# levels.net
KiCad netlist of a schematic drawn in EAGLE
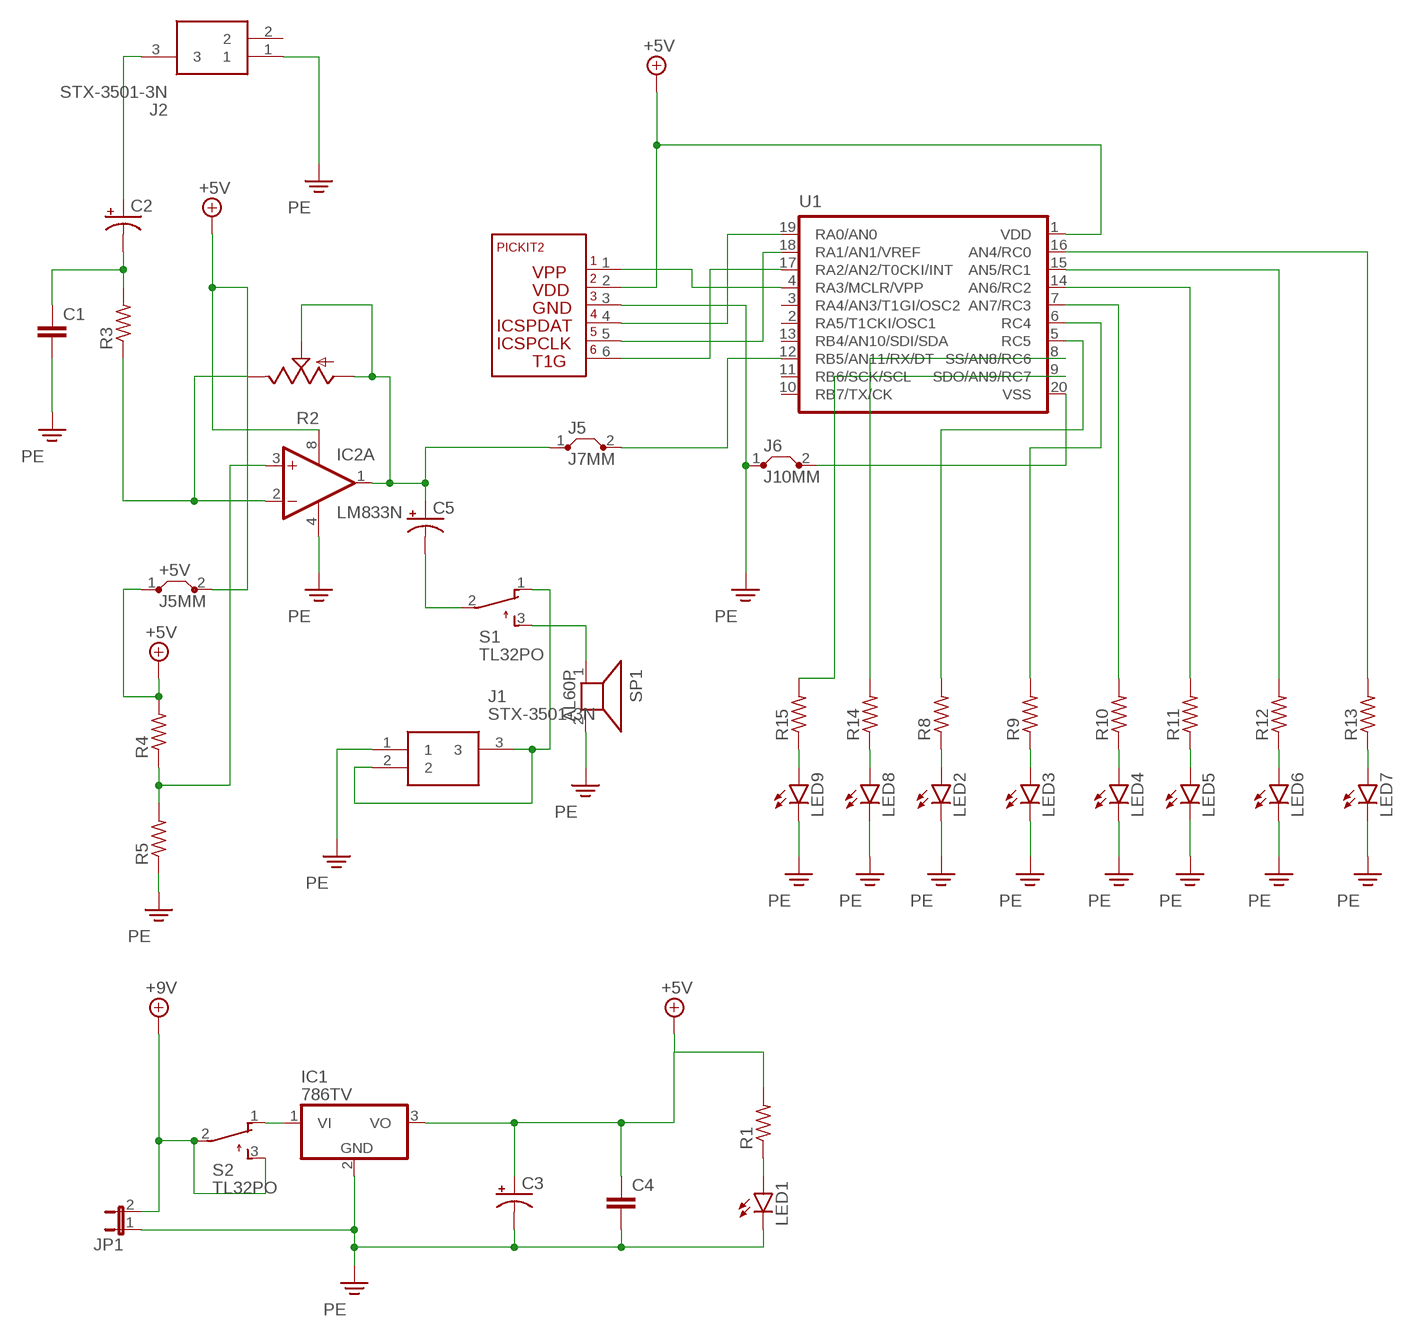
[diagram p0: schematic, sheet 1]

(export (version "E")
  (design (tool "Eeschema 10.0.6"))
  (components
    (comp (ref "+5V")
      (value "J5MM")
      (footprint "eagle-import:05")
      (libsource (lib "eagle-import") (part "J5MM"))
    )
    (comp (ref "C1")
      (value "C-EU025-024X044")
      (footprint "eagle-import:C025-024X044")
      (libsource (lib "eagle-import") (part "C-EU025-024X044"))
    )
    (comp (ref "C2")
      (value "CPOL-USE3.5-8")
      (footprint "eagle-import:E3,5-8")
      (libsource (lib "eagle-import") (part "CPOL-USE3.5-8"))
    )
    (comp (ref "C3")
      (value "CPOL-USE3.5-8")
      (footprint "eagle-import:E3,5-8")
      (libsource (lib "eagle-import") (part "CPOL-USE3.5-8"))
    )
    (comp (ref "C4")
      (value "C-EU025-024X044")
      (footprint "eagle-import:C025-024X044")
      (libsource (lib "eagle-import") (part "C-EU025-024X044"))
    )
    (comp (ref "C5")
      (value "CPOL-USE3.5-8")
      (footprint "eagle-import:E3,5-8")
      (libsource (lib "eagle-import") (part "CPOL-USE3.5-8"))
    )
    (comp (ref "IC1")
      (value "786TV")
      (footprint "eagle-import:TO220V")
      (libsource (lib "eagle-import") (part "78TV6"))
    )
    (comp (ref "IC2")
      (value "LM833N")
      (footprint "eagle-import:DIL08")
      (libsource (lib "eagle-import") (part "LM833N"))
    )
    (comp (ref "J1")
      (value "STX-3501-3N")
      (footprint "eagle-import:STX35013N")
      (fields (field (name "MF") "Kycon"))
      (libsource (lib "eagle-import") (part "STX-3501-3N"))
    )
    (comp (ref "J2")
      (value "STX-3501-3N")
      (footprint "eagle-import:STX35013N")
      (fields (field (name "MF") "Kycon"))
      (libsource (lib "eagle-import") (part "STX-3501-3N"))
    )
    (comp (ref "J5")
      (value "J7MM")
      (footprint "eagle-import:07")
      (libsource (lib "eagle-import") (part "J7MM"))
    )
    (comp (ref "J6")
      (value "J10MM")
      (footprint "eagle-import:10")
      (libsource (lib "eagle-import") (part "J10MM"))
    )
    (comp (ref "JP1")
      (value "JP1E")
      (footprint "eagle-import:JP1")
      (libsource (lib "eagle-import") (part "JP1E"))
    )
    (comp (ref "LED1")
      (value "LED5MM")
      (footprint "eagle-import:LED5MM")
      (libsource (lib "eagle-import") (part "LED5MM"))
    )
    (comp (ref "LED2")
      (value "LED5MM")
      (footprint "eagle-import:LED5MM")
      (libsource (lib "eagle-import") (part "LED5MM"))
    )
    (comp (ref "LED3")
      (value "LED5MM")
      (footprint "eagle-import:LED5MM")
      (libsource (lib "eagle-import") (part "LED5MM"))
    )
    (comp (ref "LED4")
      (value "LED5MM")
      (footprint "eagle-import:LED5MM")
      (libsource (lib "eagle-import") (part "LED5MM"))
    )
    (comp (ref "LED5")
      (value "LED5MM")
      (footprint "eagle-import:LED5MM")
      (libsource (lib "eagle-import") (part "LED5MM"))
    )
    (comp (ref "LED6")
      (value "LED5MM")
      (footprint "eagle-import:LED5MM")
      (libsource (lib "eagle-import") (part "LED5MM"))
    )
    (comp (ref "LED7")
      (value "LED5MM")
      (footprint "eagle-import:LED5MM")
      (libsource (lib "eagle-import") (part "LED5MM"))
    )
    (comp (ref "LED8")
      (value "LED5MM")
      (footprint "eagle-import:LED5MM")
      (libsource (lib "eagle-import") (part "LED5MM"))
    )
    (comp (ref "LED9")
      (value "LED5MM")
      (footprint "eagle-import:LED5MM")
      (libsource (lib "eagle-import") (part "LED5MM"))
    )
    (comp (ref "R1")
      (value "R-US_0207/10")
      (footprint "eagle-import:0207_10")
      (libsource (lib "eagle-import") (part "R-US_0207/10"))
    )
    (comp (ref "R2")
      (value "TRIM_US-CA6V")
      (footprint "eagle-import:CA6V")
      (libsource (lib "eagle-import") (part "TRIM_US-CA6V"))
    )
    (comp (ref "R3")
      (value "R-US_0207/10")
      (footprint "eagle-import:0207_10")
      (libsource (lib "eagle-import") (part "R-US_0207/10"))
    )
    (comp (ref "R4")
      (value "R-US_0207/10")
      (footprint "eagle-import:0207_10")
      (libsource (lib "eagle-import") (part "R-US_0207/10"))
    )
    (comp (ref "R5")
      (value "R-US_0207/10")
      (footprint "eagle-import:0207_10")
      (libsource (lib "eagle-import") (part "R-US_0207/10"))
    )
    (comp (ref "R8")
      (value "R-US_0207/10")
      (footprint "eagle-import:0207_10")
      (libsource (lib "eagle-import") (part "R-US_0207/10"))
    )
    (comp (ref "R9")
      (value "R-US_0207/10")
      (footprint "eagle-import:0207_10")
      (libsource (lib "eagle-import") (part "R-US_0207/10"))
    )
    (comp (ref "R10")
      (value "R-US_0207/10")
      (footprint "eagle-import:0207_10")
      (libsource (lib "eagle-import") (part "R-US_0207/10"))
    )
    (comp (ref "R11")
      (value "R-US_0207/10")
      (footprint "eagle-import:0207_10")
      (libsource (lib "eagle-import") (part "R-US_0207/10"))
    )
    (comp (ref "R12")
      (value "R-US_0207/10")
      (footprint "eagle-import:0207_10")
      (libsource (lib "eagle-import") (part "R-US_0207/10"))
    )
    (comp (ref "R13")
      (value "R-US_0207/10")
      (footprint "eagle-import:0207_10")
      (libsource (lib "eagle-import") (part "R-US_0207/10"))
    )
    (comp (ref "R14")
      (value "R-US_0207/10")
      (footprint "eagle-import:0207_10")
      (libsource (lib "eagle-import") (part "R-US_0207/10"))
    )
    (comp (ref "R15")
      (value "R-US_0207/10")
      (footprint "eagle-import:0207_10")
      (libsource (lib "eagle-import") (part "R-US_0207/10"))
    )
    (comp (ref "S1")
      (value "TL32PO")
      (footprint "eagle-import:TL3XPO")
      (libsource (lib "eagle-import") (part "TL32PO"))
    )
    (comp (ref "S2")
      (value "TL32PO")
      (footprint "eagle-import:TL3XPO")
      (libsource (lib "eagle-import") (part "TL32PO"))
    )
    (comp (ref "SP1")
      (value "AL60P")
      (footprint "eagle-import:AL60P")
      (libsource (lib "eagle-import") (part "AL60P"))
    )
    (comp (ref "U$1")
      (value "PICKIT-ICSP")
      (footprint "eagle-import:PICKITJUMPER")
      (libsource (lib "eagle-import") (part "PICKIT-ICSP"))
    )
    (comp (ref "U1")
      (value "PIC16F6XX")
      (footprint "eagle-import:DIL20")
      (libsource (lib "eagle-import") (part "PIC16F6XX"))
    )
  )
  (nets
    (net (code "1") (name "+5V") (class "Default")
      (node (ref "+5V") (pin "1") (pinfunction "1_1") (pintype "passive"))
      (node (ref "+5V") (pin "2") (pinfunction "2_2") (pintype "passive"))
      (node (ref "C3") (pin "+") (pinfunction "+_+") (pintype "passive"))
      (node (ref "C4") (pin "1") (pinfunction "1_1") (pintype "passive"))
      (node (ref "IC1") (pin "3") (pinfunction "VO_3") (pintype "passive"))
      (node (ref "IC2") (pin "8") (pinfunction "V+_8") (pintype "power_in"))
      (node (ref "R1") (pin "2") (pinfunction "2_2") (pintype "passive"))
      (node (ref "R4") (pin "2") (pinfunction "2_2") (pintype "passive"))
      (node (ref "U$1") (pin "2") (pinfunction "P$2_2") (pintype "bidirectional"))
      (node (ref "U1") (pin "1") (pinfunction "VDD_1") (pintype "power_in"))
    )
    (net (code "2") (name "+9V") (class "Default")
      (node (ref "JP1") (pin "2") (pinfunction "2_2") (pintype "passive"))
      (node (ref "S2") (pin "2") (pinfunction "P_2") (pintype "passive"))
      (node (ref "S2") (pin "3") (pinfunction "S_3") (pintype "passive"))
    )
    (net (code "3") (name "Net-(C1-Pad1)") (class "Default")
      (node (ref "C1") (pin "1") (pinfunction "1_1") (pintype "passive"))
      (node (ref "C2") (pin "-") (pinfunction "-_-") (pintype "passive"))
      (node (ref "R3") (pin "2") (pinfunction "2_2") (pintype "passive"))
    )
    (net (code "4") (name "Net-(C2-Pad+)") (class "Default")
      (node (ref "C2") (pin "+") (pinfunction "+_+") (pintype "passive"))
      (node (ref "J2") (pin "3") (pinfunction "3_3") (pintype "bidirectional"))
    )
    (net (code "5") (name "Net-(IC1-VI)") (class "Default")
      (node (ref "IC1") (pin "1") (pinfunction "VI_1") (pintype "input"))
      (node (ref "S2") (pin "1") (pinfunction "O_1") (pintype "passive"))
    )
    (net (code "6") (name "Net-(IC2A-+IN)") (class "Default")
      (node (ref "IC2") (pin "3") (pinfunction "+IN_3") (pintype "input"))
      (node (ref "R4") (pin "1") (pinfunction "1_1") (pintype "passive"))
      (node (ref "R5") (pin "2") (pinfunction "2_2") (pintype "passive"))
    )
    (net (code "7") (name "Net-(IC2A--IN)") (class "Default")
      (node (ref "IC2") (pin "2") (pinfunction "-IN_2") (pintype "input"))
      (node (ref "R2") (pin "E") (pinfunction "E_E") (pintype "passive"))
      (node (ref "R3") (pin "1") (pinfunction "1_1") (pintype "passive"))
    )
    (net (code "8") (name "Net-(IC2A-OUT)") (class "Default")
      (node (ref "C5") (pin "+") (pinfunction "+_+") (pintype "passive"))
      (node (ref "IC2") (pin "1") (pinfunction "OUT_1") (pintype "output"))
      (node (ref "J5") (pin "1") (pinfunction "1_1") (pintype "passive"))
      (node (ref "R2") (pin "A") (pinfunction "A_A") (pintype "passive"))
      (node (ref "R2") (pin "S") (pinfunction "S_S") (pintype "passive"))
    )
    (net (code "9") (name "Net-(LED1-PadA)") (class "Default")
      (node (ref "LED1") (pin "A") (pinfunction "A_A") (pintype "passive"))
      (node (ref "R1") (pin "1") (pinfunction "1_1") (pintype "passive"))
    )
    (net (code "10") (name "Net-(LED2-PadA)") (class "Default")
      (node (ref "LED2") (pin "A") (pinfunction "A_A") (pintype "passive"))
      (node (ref "R8") (pin "1") (pinfunction "1_1") (pintype "passive"))
    )
    (net (code "11") (name "Net-(LED3-PadA)") (class "Default")
      (node (ref "LED3") (pin "A") (pinfunction "A_A") (pintype "passive"))
      (node (ref "R9") (pin "1") (pinfunction "1_1") (pintype "passive"))
    )
    (net (code "12") (name "Net-(LED4-PadA)") (class "Default")
      (node (ref "LED4") (pin "A") (pinfunction "A_A") (pintype "passive"))
      (node (ref "R10") (pin "1") (pinfunction "1_1") (pintype "passive"))
    )
    (net (code "13") (name "Net-(LED5-PadA)") (class "Default")
      (node (ref "LED5") (pin "A") (pinfunction "A_A") (pintype "passive"))
      (node (ref "R11") (pin "1") (pinfunction "1_1") (pintype "passive"))
    )
    (net (code "14") (name "Net-(LED6-PadA)") (class "Default")
      (node (ref "LED6") (pin "A") (pinfunction "A_A") (pintype "passive"))
      (node (ref "R12") (pin "1") (pinfunction "1_1") (pintype "passive"))
    )
    (net (code "15") (name "Net-(LED7-PadA)") (class "Default")
      (node (ref "LED7") (pin "A") (pinfunction "A_A") (pintype "passive"))
      (node (ref "R13") (pin "1") (pinfunction "1_1") (pintype "passive"))
    )
    (net (code "16") (name "Net-(LED8-PadA)") (class "Default")
      (node (ref "LED8") (pin "A") (pinfunction "A_A") (pintype "passive"))
      (node (ref "R14") (pin "1") (pinfunction "1_1") (pintype "passive"))
    )
    (net (code "17") (name "Net-(LED9-PadA)") (class "Default")
      (node (ref "LED9") (pin "A") (pinfunction "A_A") (pintype "passive"))
      (node (ref "R15") (pin "1") (pinfunction "1_1") (pintype "passive"))
    )
    (net (code "18") (name "Net-(S1-O)") (class "Default")
      (node (ref "J1") (pin "2") (pinfunction "2_2") (pintype "bidirectional"))
      (node (ref "J1") (pin "3") (pinfunction "3_3") (pintype "bidirectional"))
      (node (ref "S1") (pin "1") (pinfunction "O_1") (pintype "passive"))
    )
    (net (code "19") (name "Net-(S1-P)") (class "Default")
      (node (ref "C5") (pin "-") (pinfunction "-_-") (pintype "passive"))
      (node (ref "S1") (pin "2") (pinfunction "P_2") (pintype "passive"))
    )
    (net (code "20") (name "Net-(S1-S)") (class "Default")
      (node (ref "S1") (pin "3") (pinfunction "S_3") (pintype "passive"))
      (node (ref "SP1") (pin "1") (pinfunction "1_1") (pintype "passive"))
    )
    (net (code "21") (name "Net-(U$1-P$4)") (class "Default")
      (node (ref "U$1") (pin "4") (pinfunction "P$4_4") (pintype "bidirectional"))
      (node (ref "U1") (pin "19") (pinfunction "RA0/AN0_19") (pintype "bidirectional"))
    )
    (net (code "22") (name "Net-(U$1-P$5)") (class "Default")
      (node (ref "U$1") (pin "5") (pinfunction "P$5_5") (pintype "bidirectional"))
      (node (ref "U1") (pin "18") (pinfunction "RA1/AN1/VREF_18") (pintype "bidirectional"))
    )
    (net (code "23") (name "Net-(U$1-P$6)") (class "Default")
      (node (ref "U$1") (pin "6") (pinfunction "P$6_6") (pintype "bidirectional"))
      (node (ref "U1") (pin "17") (pinfunction "RA2/AN2/T0CKI/INT_17") (pintype "bidirectional"))
    )
    (net (code "24") (name "Net-(U1-AN4{slash}RC0)") (class "Default")
      (node (ref "R13") (pin "2") (pinfunction "2_2") (pintype "passive"))
      (node (ref "U1") (pin "16") (pinfunction "AN4/RC0_16") (pintype "bidirectional"))
    )
    (net (code "25") (name "Net-(U1-AN5{slash}RC1)") (class "Default")
      (node (ref "R12") (pin "2") (pinfunction "2_2") (pintype "passive"))
      (node (ref "U1") (pin "15") (pinfunction "AN5/RC1_15") (pintype "bidirectional"))
    )
    (net (code "26") (name "Net-(U1-AN6{slash}RC2)") (class "Default")
      (node (ref "R11") (pin "2") (pinfunction "2_2") (pintype "passive"))
      (node (ref "U1") (pin "14") (pinfunction "AN6/RC2_14") (pintype "bidirectional"))
    )
    (net (code "27") (name "Net-(U1-AN7{slash}RC3)") (class "Default")
      (node (ref "R10") (pin "2") (pinfunction "2_2") (pintype "passive"))
      (node (ref "U1") (pin "7") (pinfunction "AN7/RC3_7") (pintype "bidirectional"))
    )
    (net (code "28") (name "Net-(U1-RA3{slash}MCLR{slash}VPP)") (class "Default")
      (node (ref "U$1") (pin "1") (pinfunction "1_1") (pintype "bidirectional"))
      (node (ref "U1") (pin "4") (pinfunction "RA3/MCLR/VPP_4") (pintype "input"))
    )
    (net (code "29") (name "Net-(U1-RB5{slash}AN11{slash}RX{slash}DT)") (class "Default")
      (node (ref "J5") (pin "2") (pinfunction "2_2") (pintype "passive"))
      (node (ref "U1") (pin "12") (pinfunction "RB5/AN11/RX/DT_12") (pintype "bidirectional"))
    )
    (net (code "30") (name "Net-(U1-RC4)") (class "Default")
      (node (ref "R9") (pin "2") (pinfunction "2_2") (pintype "passive"))
      (node (ref "U1") (pin "6") (pinfunction "RC4_6") (pintype "bidirectional"))
    )
    (net (code "31") (name "Net-(U1-RC5)") (class "Default")
      (node (ref "R8") (pin "2") (pinfunction "2_2") (pintype "passive"))
      (node (ref "U1") (pin "5") (pinfunction "RC5_5") (pintype "bidirectional"))
    )
    (net (code "32") (name "Net-(U1-SDO{slash}AN9{slash}RC7)") (class "Default")
      (node (ref "R15") (pin "2") (pinfunction "2_2") (pintype "passive"))
      (node (ref "U1") (pin "9") (pinfunction "SDO/AN9/RC7_9") (pintype "bidirectional"))
    )
    (net (code "33") (name "Net-(U1-SS{slash}AN8{slash}RC6)") (class "Default")
      (node (ref "R14") (pin "2") (pinfunction "2_2") (pintype "passive"))
      (node (ref "U1") (pin "8") (pinfunction "SS/AN8/RC6_8") (pintype "bidirectional"))
    )
    (net (code "34") (name "Net-(U1-VSS)") (class "Default")
      (node (ref "J6") (pin "2") (pinfunction "2_2") (pintype "passive"))
      (node (ref "U1") (pin "20") (pinfunction "VSS_20") (pintype "power_in"))
    )
    (net (code "35") (name "PE") (class "Default")
      (node (ref "C1") (pin "2") (pinfunction "2_2") (pintype "passive"))
      (node (ref "C3") (pin "-") (pinfunction "-_-") (pintype "passive"))
      (node (ref "C4") (pin "2") (pinfunction "2_2") (pintype "passive"))
      (node (ref "IC1") (pin "2") (pinfunction "GND_2") (pintype "passive"))
      (node (ref "IC2") (pin "4") (pinfunction "V-_4") (pintype "power_in"))
      (node (ref "J1") (pin "1") (pinfunction "1_1") (pintype "bidirectional"))
      (node (ref "J2") (pin "1") (pinfunction "1_1") (pintype "bidirectional"))
      (node (ref "J6") (pin "1") (pinfunction "1_1") (pintype "passive"))
      (node (ref "JP1") (pin "1") (pinfunction "1_1") (pintype "passive"))
      (node (ref "LED1") (pin "K") (pinfunction "C_K") (pintype "passive"))
      (node (ref "LED2") (pin "K") (pinfunction "C_K") (pintype "passive"))
      (node (ref "LED3") (pin "K") (pinfunction "C_K") (pintype "passive"))
      (node (ref "LED4") (pin "K") (pinfunction "C_K") (pintype "passive"))
      (node (ref "LED5") (pin "K") (pinfunction "C_K") (pintype "passive"))
      (node (ref "LED6") (pin "K") (pinfunction "C_K") (pintype "passive"))
      (node (ref "LED7") (pin "K") (pinfunction "C_K") (pintype "passive"))
      (node (ref "LED8") (pin "K") (pinfunction "C_K") (pintype "passive"))
      (node (ref "LED9") (pin "K") (pinfunction "C_K") (pintype "passive"))
      (node (ref "R5") (pin "1") (pinfunction "1_1") (pintype "passive"))
      (node (ref "SP1") (pin "2") (pinfunction "2_2") (pintype "passive"))
      (node (ref "U$1") (pin "3") (pinfunction "P$3_3") (pintype "bidirectional"))
    )
    (net (code "36") (name "unconnected-(J2-Pad2)") (class "Default")
      (node (ref "J2") (pin "2") (pinfunction "2_2") (pintype "bidirectional"))
    )
    (net (code "37") (name "unconnected-(U1-RA4{slash}AN3{slash}T1GI{slash}OSC2-Pad3)") (class "Default")
      (node (ref "U1") (pin "3") (pinfunction "RA4/AN3/T1GI/OSC2_3") (pintype "bidirectional"))
    )
    (net (code "38") (name "unconnected-(U1-RA5{slash}T1CKI{slash}OSC1-Pad2)") (class "Default")
      (node (ref "U1") (pin "2") (pinfunction "RA5/T1CKI/OSC1_2") (pintype "bidirectional"))
    )
    (net (code "39") (name "unconnected-(U1-RB4{slash}AN10{slash}SDI{slash}SDA-Pad13)") (class "Default")
      (node (ref "U1") (pin "13") (pinfunction "RB4/AN10/SDI/SDA_13") (pintype "bidirectional"))
    )
    (net (code "40") (name "unconnected-(U1-RB6{slash}SCK{slash}SCL-Pad11)") (class "Default")
      (node (ref "U1") (pin "11") (pinfunction "RB6/SCK/SCL_11") (pintype "bidirectional"))
    )
    (net (code "41") (name "unconnected-(U1-RB7{slash}TX{slash}CK-Pad10)") (class "Default")
      (node (ref "U1") (pin "10") (pinfunction "RB7/TX/CK_10") (pintype "bidirectional"))
    )
  )
)
